# Test_pistes.net
KiCad netlist of a schematic drawn in EAGLE
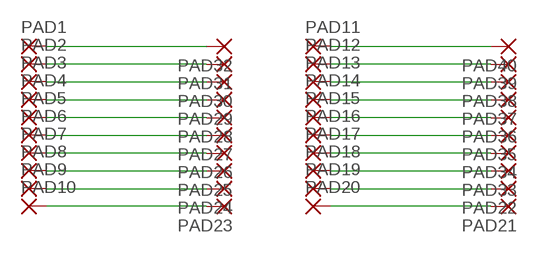
[diagram p0: schematic, sheet 1]

(export (version "E")
  (design (tool "Eeschema 10.0.6"))
  (components
    (comp (ref "PAD1")
      (value "2,54/1,1")
      (footprint "eagle-import:2,54_1,1")
      (libsource (lib "eagle-import") (part "2,54/1,1"))
    )
    (comp (ref "PAD2")
      (value "2,54/1,1")
      (footprint "eagle-import:2,54_1,1")
      (libsource (lib "eagle-import") (part "2,54/1,1"))
    )
    (comp (ref "PAD3")
      (value "2,54/1,1")
      (footprint "eagle-import:2,54_1,1")
      (libsource (lib "eagle-import") (part "2,54/1,1"))
    )
    (comp (ref "PAD4")
      (value "2,54/1,1")
      (footprint "eagle-import:2,54_1,1")
      (libsource (lib "eagle-import") (part "2,54/1,1"))
    )
    (comp (ref "PAD5")
      (value "2,54/1,1")
      (footprint "eagle-import:2,54_1,1")
      (libsource (lib "eagle-import") (part "2,54/1,1"))
    )
    (comp (ref "PAD6")
      (value "2,54/1,1")
      (footprint "eagle-import:2,54_1,1")
      (libsource (lib "eagle-import") (part "2,54/1,1"))
    )
    (comp (ref "PAD7")
      (value "2,54/1,1")
      (footprint "eagle-import:2,54_1,1")
      (libsource (lib "eagle-import") (part "2,54/1,1"))
    )
    (comp (ref "PAD8")
      (value "2,54/1,1")
      (footprint "eagle-import:2,54_1,1")
      (libsource (lib "eagle-import") (part "2,54/1,1"))
    )
    (comp (ref "PAD9")
      (value "2,54/1,1")
      (footprint "eagle-import:2,54_1,1")
      (libsource (lib "eagle-import") (part "2,54/1,1"))
    )
    (comp (ref "PAD10")
      (value "2,54/1,1")
      (footprint "eagle-import:2,54_1,1")
      (libsource (lib "eagle-import") (part "2,54/1,1"))
    )
    (comp (ref "PAD11")
      (value "2,54/1,1")
      (footprint "eagle-import:2,54_1,1")
      (libsource (lib "eagle-import") (part "2,54/1,1"))
    )
    (comp (ref "PAD12")
      (value "2,54/1,1")
      (footprint "eagle-import:2,54_1,1")
      (libsource (lib "eagle-import") (part "2,54/1,1"))
    )
    (comp (ref "PAD13")
      (value "2,54/1,1")
      (footprint "eagle-import:2,54_1,1")
      (libsource (lib "eagle-import") (part "2,54/1,1"))
    )
    (comp (ref "PAD14")
      (value "2,54/1,1")
      (footprint "eagle-import:2,54_1,1")
      (libsource (lib "eagle-import") (part "2,54/1,1"))
    )
    (comp (ref "PAD15")
      (value "2,54/1,1")
      (footprint "eagle-import:2,54_1,1")
      (libsource (lib "eagle-import") (part "2,54/1,1"))
    )
    (comp (ref "PAD16")
      (value "2,54/1,1")
      (footprint "eagle-import:2,54_1,1")
      (libsource (lib "eagle-import") (part "2,54/1,1"))
    )
    (comp (ref "PAD17")
      (value "2,54/1,1")
      (footprint "eagle-import:2,54_1,1")
      (libsource (lib "eagle-import") (part "2,54/1,1"))
    )
    (comp (ref "PAD18")
      (value "2,54/1,1")
      (footprint "eagle-import:2,54_1,1")
      (libsource (lib "eagle-import") (part "2,54/1,1"))
    )
    (comp (ref "PAD19")
      (value "2,54/1,1")
      (footprint "eagle-import:2,54_1,1")
      (libsource (lib "eagle-import") (part "2,54/1,1"))
    )
    (comp (ref "PAD20")
      (value "2,54/1,1")
      (footprint "eagle-import:2,54_1,1")
      (libsource (lib "eagle-import") (part "2,54/1,1"))
    )
    (comp (ref "PAD21")
      (value "2,54/1,1")
      (footprint "eagle-import:2,54_1,1")
      (libsource (lib "eagle-import") (part "2,54/1,1"))
    )
    (comp (ref "PAD22")
      (value "2,54/1,1")
      (footprint "eagle-import:2,54_1,1")
      (libsource (lib "eagle-import") (part "2,54/1,1"))
    )
    (comp (ref "PAD23")
      (value "2,54/1,1")
      (footprint "eagle-import:2,54_1,1")
      (libsource (lib "eagle-import") (part "2,54/1,1"))
    )
    (comp (ref "PAD24")
      (value "2,54/1,1")
      (footprint "eagle-import:2,54_1,1")
      (libsource (lib "eagle-import") (part "2,54/1,1"))
    )
    (comp (ref "PAD25")
      (value "2,54/1,1")
      (footprint "eagle-import:2,54_1,1")
      (libsource (lib "eagle-import") (part "2,54/1,1"))
    )
    (comp (ref "PAD26")
      (value "2,54/1,1")
      (footprint "eagle-import:2,54_1,1")
      (libsource (lib "eagle-import") (part "2,54/1,1"))
    )
    (comp (ref "PAD27")
      (value "2,54/1,1")
      (footprint "eagle-import:2,54_1,1")
      (libsource (lib "eagle-import") (part "2,54/1,1"))
    )
    (comp (ref "PAD28")
      (value "2,54/1,1")
      (footprint "eagle-import:2,54_1,1")
      (libsource (lib "eagle-import") (part "2,54/1,1"))
    )
    (comp (ref "PAD29")
      (value "2,54/1,1")
      (footprint "eagle-import:2,54_1,1")
      (libsource (lib "eagle-import") (part "2,54/1,1"))
    )
    (comp (ref "PAD30")
      (value "2,54/1,1")
      (footprint "eagle-import:2,54_1,1")
      (libsource (lib "eagle-import") (part "2,54/1,1"))
    )
    (comp (ref "PAD31")
      (value "2,54/1,1")
      (footprint "eagle-import:2,54_1,1")
      (libsource (lib "eagle-import") (part "2,54/1,1"))
    )
    (comp (ref "PAD32")
      (value "2,54/1,1")
      (footprint "eagle-import:2,54_1,1")
      (libsource (lib "eagle-import") (part "2,54/1,1"))
    )
    (comp (ref "PAD33")
      (value "2,54/1,1")
      (footprint "eagle-import:2,54_1,1")
      (libsource (lib "eagle-import") (part "2,54/1,1"))
    )
    (comp (ref "PAD34")
      (value "2,54/1,1")
      (footprint "eagle-import:2,54_1,1")
      (libsource (lib "eagle-import") (part "2,54/1,1"))
    )
    (comp (ref "PAD35")
      (value "2,54/1,1")
      (footprint "eagle-import:2,54_1,1")
      (libsource (lib "eagle-import") (part "2,54/1,1"))
    )
    (comp (ref "PAD36")
      (value "2,54/1,1")
      (footprint "eagle-import:2,54_1,1")
      (libsource (lib "eagle-import") (part "2,54/1,1"))
    )
    (comp (ref "PAD37")
      (value "2,54/1,1")
      (footprint "eagle-import:2,54_1,1")
      (libsource (lib "eagle-import") (part "2,54/1,1"))
    )
    (comp (ref "PAD38")
      (value "2,54/1,1")
      (footprint "eagle-import:2,54_1,1")
      (libsource (lib "eagle-import") (part "2,54/1,1"))
    )
    (comp (ref "PAD39")
      (value "2,54/1,1")
      (footprint "eagle-import:2,54_1,1")
      (libsource (lib "eagle-import") (part "2,54/1,1"))
    )
    (comp (ref "PAD40")
      (value "2,54/1,1")
      (footprint "eagle-import:2,54_1,1")
      (libsource (lib "eagle-import") (part "2,54/1,1"))
    )
  )
  (nets
    (net (code "1") (name "Net-(PAD1-P)") (class "Default")
      (node (ref "PAD1") (pin "1") (pinfunction "P_1") (pintype "passive"))
      (node (ref "PAD32") (pin "1") (pinfunction "P_1") (pintype "passive"))
    )
    (net (code "2") (name "Net-(PAD2-P)") (class "Default")
      (node (ref "PAD2") (pin "1") (pinfunction "P_1") (pintype "passive"))
      (node (ref "PAD31") (pin "1") (pinfunction "P_1") (pintype "passive"))
    )
    (net (code "3") (name "Net-(PAD3-P)") (class "Default")
      (node (ref "PAD3") (pin "1") (pinfunction "P_1") (pintype "passive"))
      (node (ref "PAD30") (pin "1") (pinfunction "P_1") (pintype "passive"))
    )
    (net (code "4") (name "Net-(PAD10-P)") (class "Default")
      (node (ref "PAD10") (pin "1") (pinfunction "P_1") (pintype "passive"))
      (node (ref "PAD23") (pin "1") (pinfunction "P_1") (pintype "passive"))
    )
    (net (code "5") (name "Net-(PAD11-P)") (class "Default")
      (node (ref "PAD11") (pin "1") (pinfunction "P_1") (pintype "passive"))
      (node (ref "PAD40") (pin "1") (pinfunction "P_1") (pintype "passive"))
    )
    (net (code "6") (name "Net-(PAD12-P)") (class "Default")
      (node (ref "PAD12") (pin "1") (pinfunction "P_1") (pintype "passive"))
      (node (ref "PAD39") (pin "1") (pinfunction "P_1") (pintype "passive"))
    )
    (net (code "7") (name "Net-(PAD13-P)") (class "Default")
      (node (ref "PAD13") (pin "1") (pinfunction "P_1") (pintype "passive"))
      (node (ref "PAD38") (pin "1") (pinfunction "P_1") (pintype "passive"))
    )
    (net (code "8") (name "Net-(PAD14-P)") (class "Default")
      (node (ref "PAD14") (pin "1") (pinfunction "P_1") (pintype "passive"))
      (node (ref "PAD37") (pin "1") (pinfunction "P_1") (pintype "passive"))
    )
    (net (code "9") (name "Net-(PAD15-P)") (class "Default")
      (node (ref "PAD15") (pin "1") (pinfunction "P_1") (pintype "passive"))
      (node (ref "PAD36") (pin "1") (pinfunction "P_1") (pintype "passive"))
    )
    (net (code "10") (name "Net-(PAD16-P)") (class "Default")
      (node (ref "PAD16") (pin "1") (pinfunction "P_1") (pintype "passive"))
      (node (ref "PAD35") (pin "1") (pinfunction "P_1") (pintype "passive"))
    )
    (net (code "11") (name "Net-(PAD17-P)") (class "Default")
      (node (ref "PAD17") (pin "1") (pinfunction "P_1") (pintype "passive"))
      (node (ref "PAD34") (pin "1") (pinfunction "P_1") (pintype "passive"))
    )
    (net (code "12") (name "Net-(PAD18-P)") (class "Default")
      (node (ref "PAD18") (pin "1") (pinfunction "P_1") (pintype "passive"))
      (node (ref "PAD33") (pin "1") (pinfunction "P_1") (pintype "passive"))
    )
    (net (code "13") (name "Net-(PAD19-P)") (class "Default")
      (node (ref "PAD19") (pin "1") (pinfunction "P_1") (pintype "passive"))
      (node (ref "PAD22") (pin "1") (pinfunction "P_1") (pintype "passive"))
    )
    (net (code "14") (name "Net-(PAD20-P)") (class "Default")
      (node (ref "PAD20") (pin "1") (pinfunction "P_1") (pintype "passive"))
      (node (ref "PAD21") (pin "1") (pinfunction "P_1") (pintype "passive"))
    )
    (net (code "15") (name "Net-(PAD24-P)") (class "Default")
      (node (ref "PAD24") (pin "1") (pinfunction "P_1") (pintype "passive"))
      (node (ref "PAD9") (pin "1") (pinfunction "P_1") (pintype "passive"))
    )
    (net (code "16") (name "Net-(PAD25-P)") (class "Default")
      (node (ref "PAD25") (pin "1") (pinfunction "P_1") (pintype "passive"))
      (node (ref "PAD8") (pin "1") (pinfunction "P_1") (pintype "passive"))
    )
    (net (code "17") (name "Net-(PAD26-P)") (class "Default")
      (node (ref "PAD26") (pin "1") (pinfunction "P_1") (pintype "passive"))
      (node (ref "PAD7") (pin "1") (pinfunction "P_1") (pintype "passive"))
    )
    (net (code "18") (name "Net-(PAD27-P)") (class "Default")
      (node (ref "PAD27") (pin "1") (pinfunction "P_1") (pintype "passive"))
      (node (ref "PAD6") (pin "1") (pinfunction "P_1") (pintype "passive"))
    )
    (net (code "19") (name "Net-(PAD28-P)") (class "Default")
      (node (ref "PAD28") (pin "1") (pinfunction "P_1") (pintype "passive"))
      (node (ref "PAD5") (pin "1") (pinfunction "P_1") (pintype "passive"))
    )
    (net (code "20") (name "Net-(PAD29-P)") (class "Default")
      (node (ref "PAD29") (pin "1") (pinfunction "P_1") (pintype "passive"))
      (node (ref "PAD4") (pin "1") (pinfunction "P_1") (pintype "passive"))
    )
  )
)
